# Sheet_1_2022-08-28.net
KiCad netlist of a schematic drawn in Altium Designer
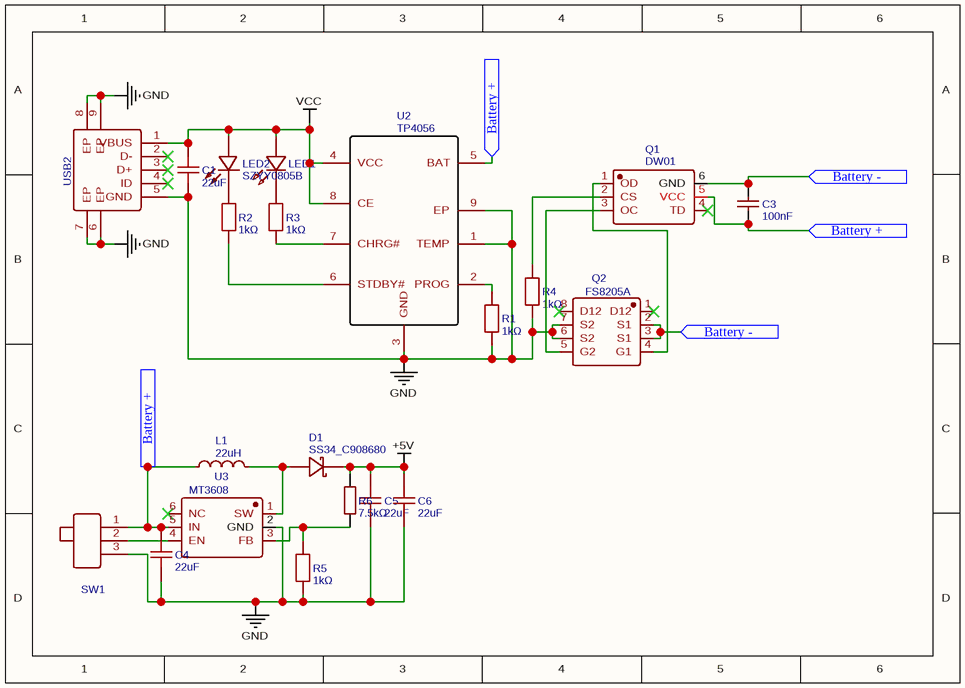
[diagram p0: Sheet_1_2022-08-28.schdoc]

(export (version "E")
  (design (tool "Eeschema 10.0.6"))
  (components
    (comp (ref "C1")
      (value "22uF")
      (fields
        (field (name "BOM_MANUFACTURER PART") "0805F226M250NT")
        (field (name "BOM_SUPPLIER PART") "C161205")
        (field (name "CONTRIBUTOR") "LCSC")
      )
      (libsource (lib "altium-import") (part "root_1_22uF_"))
    )
    (comp (ref "C3")
      (value "100nF")
      (fields
        (field (name "BOM_MANUFACTURER PART") "0805B104J500NT")
        (field (name "BOM_SUPPLIER PART") "C29926")
      )
      (libsource (lib "altium-import") (part "root_3_100nF_"))
    )
    (comp (ref "C4")
      (value "22uF")
      (fields
        (field (name "BOM_MANUFACTURER PART") "0805F226M250NT")
        (field (name "BOM_SUPPLIER PART") "C161205")
        (field (name "CONTRIBUTOR") "LCSC")
      )
      (libsource (lib "altium-import") (part "root_1_22uF_"))
    )
    (comp (ref "C5")
      (value "22uF")
      (fields
        (field (name "BOM_MANUFACTURER PART") "0805F226M250NT")
        (field (name "BOM_SUPPLIER PART") "C161205")
        (field (name "CONTRIBUTOR") "LCSC")
      )
      (libsource (lib "altium-import") (part "root_1_22uF_"))
    )
    (comp (ref "C6")
      (value "22uF")
      (fields
        (field (name "BOM_MANUFACTURER PART") "0805F226M250NT")
        (field (name "BOM_SUPPLIER PART") "C161205")
        (field (name "CONTRIBUTOR") "LCSC")
      )
      (libsource (lib "altium-import") (part "root_1_22uF_"))
    )
    (comp (ref "D1")
      (value "SS34_C908680")
      (fields
        (field (name "BOM_SUPPLIER PART") "C908680")
        (field (name "BOM_MANUFACTURER PART") "SS34")
        (field (name "CONTRIBUTOR") "LCSC")
      )
      (libsource (lib "altium-import") (part "root_2_SS34_C908680_"))
    )
    (comp (ref "L1")
      (value "22uH")
      (fields
        (field (name "BOM_SUPPLIER PART") "C354640")
        (field (name "BOM_MANUFACTURER PART") "CKCS8040-22uH/M")
        (field (name "CONTRIBUTOR") "LCSC")
      )
      (libsource (lib "altium-import") (part "root_0_22uH_"))
    )
    (comp (ref "LED1")
      (value "TZ-P2-0805RTCS2-0.8T")
      (fields (field (name "BOM_SUPPLIER PART") "C688884") (field (name "CONTRIBUTOR") "LCSC"))
      (libsource (lib "altium-import") (part "root_1_TZ-P2-0805RTCS2-0.8T_"))
    )
    (comp (ref "LED2")
      (value "SZYY0805B")
      (fields (field (name "BOM_SUPPLIER PART") "C434433") (field (name "CONTRIBUTOR") "LCSC"))
      (libsource (lib "altium-import") (part "root_1_SZYY0805B_"))
    )
    (comp (ref "Q1")
      (value "DW01")
      (fields (field (name "BOM_SUPPLIER PART") "C181096") (field (name "CONTRIBUTOR") "LCSC"))
      (libsource (lib "altium-import") (part "root_0_DW01_"))
    )
    (comp (ref "Q2")
      (value "FS8205A")
      (fields (field (name "BOM_SUPPLIER PART") "C16052"))
      (libsource (lib "altium-import") (part "root_0_FS8205A_"))
    )
    (comp (ref "R1")
      (value "1kΩ")
      (fields
        (field (name "BOM_SUPPLIER PART") "C374884")
        (field (name "BOM_MANUFACTURER PART") "PTFR0805D1K00P9")
        (field (name "CONTRIBUTOR") "LCSC")
      )
      (libsource (lib "altium-import") (part "root_1_1kΩ_"))
    )
    (comp (ref "R2")
      (value "1kΩ")
      (fields
        (field (name "BOM_SUPPLIER PART") "C374884")
        (field (name "BOM_MANUFACTURER PART") "PTFR0805D1K00P9")
        (field (name "CONTRIBUTOR") "LCSC")
      )
      (libsource (lib "altium-import") (part "root_1_1kΩ_"))
    )
    (comp (ref "R3")
      (value "1kΩ")
      (fields
        (field (name "BOM_SUPPLIER PART") "C374884")
        (field (name "BOM_MANUFACTURER PART") "PTFR0805D1K00P9")
        (field (name "CONTRIBUTOR") "LCSC")
      )
      (libsource (lib "altium-import") (part "root_1_1kΩ_"))
    )
    (comp (ref "R4")
      (value "1kΩ")
      (fields
        (field (name "BOM_SUPPLIER PART") "C374884")
        (field (name "BOM_MANUFACTURER PART") "PTFR0805D1K00P9")
        (field (name "CONTRIBUTOR") "LCSC")
      )
      (libsource (lib "altium-import") (part "root_1_1kΩ_"))
    )
    (comp (ref "R5")
      (value "1kΩ")
      (fields
        (field (name "BOM_SUPPLIER PART") "C374884")
        (field (name "BOM_MANUFACTURER PART") "PTFR0805D1K00P9")
        (field (name "CONTRIBUTOR") "LCSC")
      )
      (libsource (lib "altium-import") (part "root_1_1kΩ_"))
    )
    (comp (ref "R6")
      (value "7.5kΩ")
      (fields
        (field (name "BOM_MANUFACTURER PART") "0805W8J0752T5E")
        (field (name "BOM_SUPPLIER PART") "C26027")
      )
      (libsource (lib "altium-import") (part "root_1_7.5kΩ_"))
    )
    (comp (ref "SW1")
      (value "MK-12D18-G020")
      (fields (field (name "BOM_SUPPLIER PART") "C3019727") (field (name "CONTRIBUTOR") "lcsc"))
      (libsource (lib "altium-import") (part "root_1_MK-12D18-G020_"))
    )
    (comp (ref "U2")
      (value "TP4056")
      (fields (field (name "BOM_SUPPLIER PART") "C16581") (field (name "CONTRIBUTOR") "Guest"))
      (libsource (lib "altium-import") (part "root_0_TP4056_"))
    )
    (comp (ref "U3")
      (value "MT3608")
      (fields (field (name "BOM_SUPPLIER PART") "C84817"))
      (libsource (lib "altium-import") (part "root_0_MT3608_"))
    )
    (comp (ref "USB2")
      (value "U-F-M5DS-Y-2")
      (fields (field (name "BOM_SUPPLIER PART") "C94901") (field (name "CONTRIBUTOR") "LCSC"))
      (libsource (lib "altium-import") (part "root_2_U-F-M5DS-Y-2_"))
    )
  )
  (nets
    (net (code "1") (name "+5V") (class "Default")
      (node (ref "C5") (pin "1") (pinfunction "1_1") (pintype "passive"))
      (node (ref "C6") (pin "1") (pinfunction "1_1") (pintype "passive"))
      (node (ref "D1") (pin "1") (pinfunction "C_1") (pintype "passive"))
      (node (ref "R6") (pin "2") (pinfunction "2_2") (pintype "passive"))
    )
    (net (code "2") (name "/Battery +") (class "Default")
      (node (ref "C3") (pin "2") (pinfunction "2_2") (pintype "passive"))
      (node (ref "C4") (pin "1") (pinfunction "1_1") (pintype "passive"))
      (node (ref "L1") (pin "1") (pinfunction "1_1") (pintype "passive"))
      (node (ref "Q1") (pin "5") (pinfunction "VCC_5") (pintype "passive"))
      (node (ref "SW1") (pin "1") (pinfunction "1_1") (pintype "passive"))
      (node (ref "U2") (pin "5") (pinfunction "BAT_5") (pintype "passive"))
      (node (ref "U3") (pin "5") (pinfunction "IN_5") (pintype "passive"))
    )
    (net (code "3") (name "/Battery -") (class "Default")
      (node (ref "C3") (pin "1") (pinfunction "1_1") (pintype "passive"))
      (node (ref "Q1") (pin "6") (pinfunction "GND_6") (pintype "passive"))
      (node (ref "Q2") (pin "2") (pinfunction "S1_2") (pintype "passive"))
      (node (ref "Q2") (pin "3") (pinfunction "S1_3") (pintype "passive"))
    )
    (net (code "4") (name "GND") (class "Default")
      (node (ref "C1") (pin "2") (pinfunction "2_2") (pintype "passive"))
      (node (ref "C4") (pin "2") (pinfunction "2_2") (pintype "passive"))
      (node (ref "C5") (pin "2") (pinfunction "2_2") (pintype "passive"))
      (node (ref "C6") (pin "2") (pinfunction "2_2") (pintype "passive"))
      (node (ref "Q2") (pin "6") (pinfunction "S2_6") (pintype "passive"))
      (node (ref "Q2") (pin "7") (pinfunction "S2_7") (pintype "passive"))
      (node (ref "R1") (pin "1") (pinfunction "1_1") (pintype "passive"))
      (node (ref "R4") (pin "1") (pinfunction "1_1") (pintype "passive"))
      (node (ref "R5") (pin "1") (pinfunction "1_1") (pintype "passive"))
      (node (ref "SW1") (pin "3") (pinfunction "3_3") (pintype "passive"))
      (node (ref "U2") (pin "1") (pinfunction "TEMP_1") (pintype "passive"))
      (node (ref "U2") (pin "3") (pinfunction "GND_3") (pintype "passive"))
      (node (ref "U2") (pin "9") (pinfunction "EP_9") (pintype "passive"))
      (node (ref "U3") (pin "2") (pinfunction "GND_2") (pintype "passive"))
      (node (ref "USB2") (pin "5") (pinfunction "GND_5") (pintype "passive"))
      (node (ref "USB2") (pin "6") (pinfunction "EP_6") (pintype "passive"))
      (node (ref "USB2") (pin "7") (pinfunction "EP_7") (pintype "passive"))
      (node (ref "USB2") (pin "8") (pinfunction "EP_8") (pintype "passive"))
      (node (ref "USB2") (pin "9") (pinfunction "EP_9") (pintype "passive"))
    )
    (net (code "5") (name "Net-(D1-A)") (class "Default")
      (node (ref "D1") (pin "2") (pinfunction "A_2") (pintype "passive"))
      (node (ref "L1") (pin "2") (pinfunction "2_2") (pintype "passive"))
      (node (ref "U3") (pin "1") (pinfunction "SW_1") (pintype "passive"))
    )
    (net (code "6") (name "Net-(LED1-K)") (class "Default")
      (node (ref "LED1") (pin "1") (pinfunction "K_1") (pintype "passive"))
      (node (ref "R3") (pin "2") (pinfunction "2_2") (pintype "passive"))
    )
    (net (code "7") (name "Net-(LED2--)") (class "Default")
      (node (ref "LED2") (pin "2") (pinfunction "-_2") (pintype "passive"))
      (node (ref "R2") (pin "2") (pinfunction "2_2") (pintype "passive"))
    )
    (net (code "8") (name "Net-(Q1-CS)") (class "Default")
      (node (ref "Q1") (pin "2") (pinfunction "CS_2") (pintype "passive"))
      (node (ref "R4") (pin "2") (pinfunction "2_2") (pintype "passive"))
    )
    (net (code "9") (name "Net-(Q1-OC)") (class "Default")
      (node (ref "Q1") (pin "3") (pinfunction "OC_3") (pintype "passive"))
      (node (ref "Q2") (pin "5") (pinfunction "G2_5") (pintype "passive"))
    )
    (net (code "10") (name "Net-(Q1-OD)") (class "Default")
      (node (ref "Q1") (pin "1") (pinfunction "OD_1") (pintype "passive"))
      (node (ref "Q2") (pin "4") (pinfunction "G1_4") (pintype "passive"))
    )
    (net (code "11") (name "Net-(U2-CHRG#)") (class "Default")
      (node (ref "R3") (pin "1") (pinfunction "1_1") (pintype "passive"))
      (node (ref "U2") (pin "7") (pinfunction "CHRG#_7") (pintype "passive"))
    )
    (net (code "12") (name "Net-(U2-PROG)") (class "Default")
      (node (ref "R1") (pin "2") (pinfunction "2_2") (pintype "passive"))
      (node (ref "U2") (pin "2") (pinfunction "PROG_2") (pintype "passive"))
    )
    (net (code "13") (name "Net-(U2-STDBY#)") (class "Default")
      (node (ref "R2") (pin "1") (pinfunction "1_1") (pintype "passive"))
      (node (ref "U2") (pin "6") (pinfunction "STDBY#_6") (pintype "passive"))
    )
    (net (code "14") (name "Net-(U3-EN)") (class "Default")
      (node (ref "SW1") (pin "2") (pinfunction "2_2") (pintype "passive"))
      (node (ref "U3") (pin "4") (pinfunction "EN_4") (pintype "passive"))
    )
    (net (code "15") (name "Net-(U3-FB)") (class "Default")
      (node (ref "R5") (pin "2") (pinfunction "2_2") (pintype "passive"))
      (node (ref "R6") (pin "1") (pinfunction "1_1") (pintype "passive"))
      (node (ref "U3") (pin "3") (pinfunction "FB_3") (pintype "passive"))
    )
    (net (code "16") (name "VCC") (class "Default")
      (node (ref "C1") (pin "1") (pinfunction "1_1") (pintype "passive"))
      (node (ref "LED1") (pin "2") (pinfunction "A_2") (pintype "passive"))
      (node (ref "LED2") (pin "1") (pinfunction "+_1") (pintype "passive"))
      (node (ref "U2") (pin "4") (pinfunction "VCC_4") (pintype "passive"))
      (node (ref "U2") (pin "8") (pinfunction "CE_8") (pintype "passive"))
      (node (ref "USB2") (pin "1") (pinfunction "VBUS_1") (pintype "passive"))
    )
    (net (code "17") (name "unconnected-(Q1-TD-Pad4)") (class "Default")
      (node (ref "Q1") (pin "4") (pinfunction "TD_4") (pintype "passive+no_connect"))
    )
    (net (code "18") (name "unconnected-(Q2-D12-Pad1)") (class "Default")
      (node (ref "Q2") (pin "1") (pinfunction "D12_1") (pintype "passive+no_connect"))
    )
    (net (code "19") (name "unconnected-(Q2-D12-Pad8)") (class "Default")
      (node (ref "Q2") (pin "8") (pinfunction "D12_8") (pintype "passive+no_connect"))
    )
    (net (code "20") (name "unconnected-(U3-NC-Pad6)") (class "Default")
      (node (ref "U3") (pin "6") (pinfunction "NC_6") (pintype "passive+no_connect"))
    )
    (net (code "21") (name "unconnected-(USB2-D+-Pad3)") (class "Default")
      (node (ref "USB2") (pin "3") (pinfunction "D+_3") (pintype "passive+no_connect"))
    )
    (net (code "22") (name "unconnected-(USB2-D--Pad2)") (class "Default")
      (node (ref "USB2") (pin "2") (pinfunction "D-_2") (pintype "passive+no_connect"))
    )
    (net (code "23") (name "unconnected-(USB2-ID-Pad4)") (class "Default")
      (node (ref "USB2") (pin "4") (pinfunction "ID_4") (pintype "passive+no_connect"))
    )
  )
)
